# SakuraIo.net
KiCad netlist of a schematic drawn in EAGLE
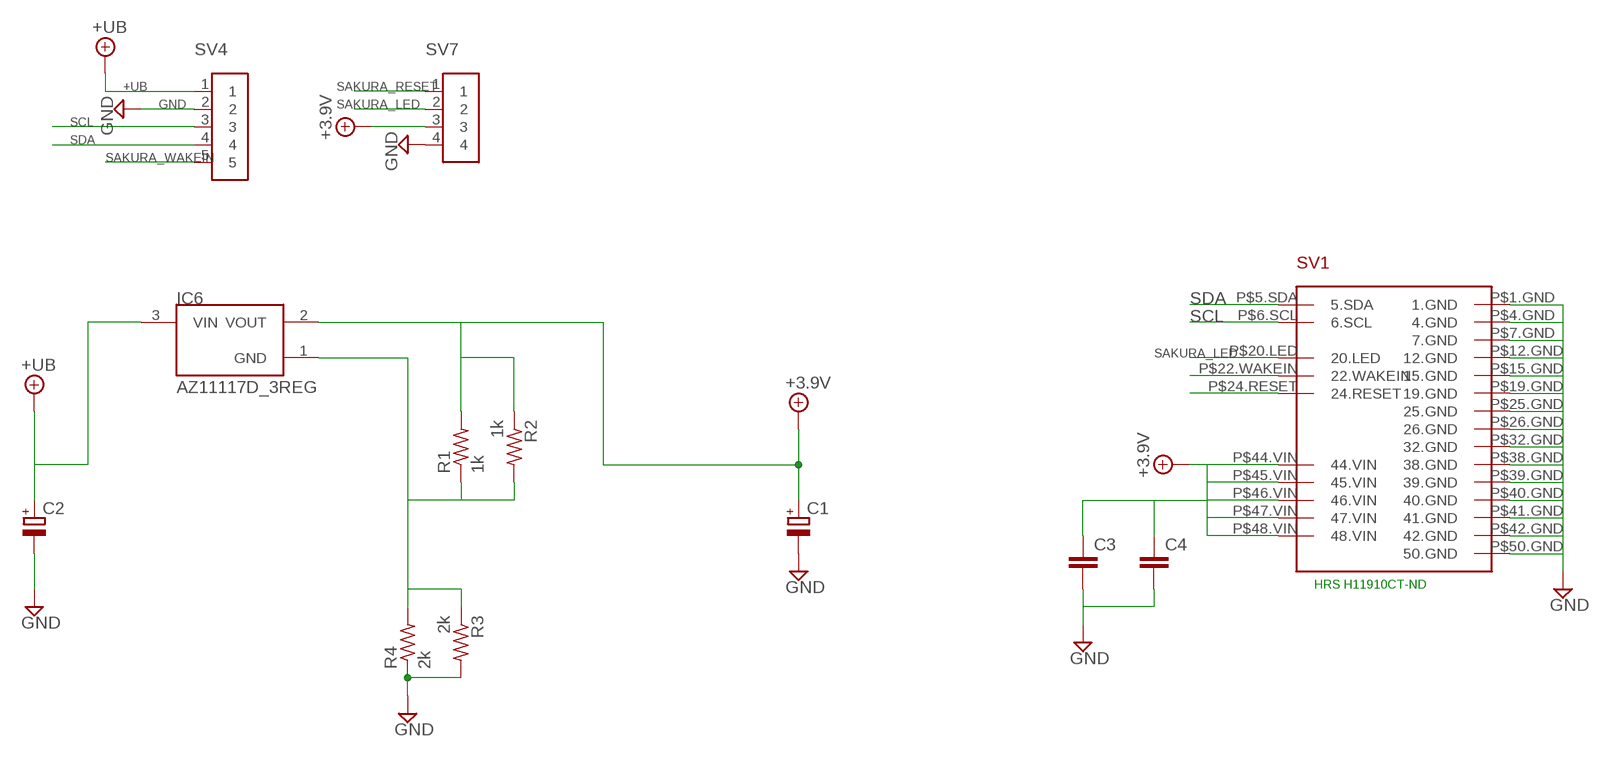
[diagram p0: schematic, sheet 1]

(export (version "E")
  (design (tool "Eeschema 10.0.6"))
  (components
    (comp (ref "C1")
      (value "CPOL-EUE2,5-6E")
      (footprint "eagle-import:E2,5-6E")
      (libsource (lib "eagle-import") (part "CPOL-EUE2,5-6E"))
    )
    (comp (ref "C2")
      (value "CPOL-EUE2,5-6E")
      (footprint "eagle-import:E2,5-6E")
      (libsource (lib "eagle-import") (part "CPOL-EUE2,5-6E"))
    )
    (comp (ref "C3")
      (value "C-EUC0603")
      (footprint "eagle-import:C0603")
      (libsource (lib "eagle-import") (part "C-EUC0603"))
    )
    (comp (ref "C4")
      (value "C-EUC0603")
      (footprint "eagle-import:C0603")
      (libsource (lib "eagle-import") (part "C-EUC0603"))
    )
    (comp (ref "IC6")
      (value "AZ11117D_3REG")
      (footprint "eagle-import:TO252")
      (libsource (lib "eagle-import") (part "AZ11117D_3REG"))
    )
    (comp (ref "R1")
      (value "1k")
      (footprint "eagle-import:0204_7")
      (libsource (lib "eagle-import") (part "R-US_0204/7"))
    )
    (comp (ref "R2")
      (value "1k")
      (footprint "eagle-import:R0603")
      (libsource (lib "eagle-import") (part "resistor_R-US_R0603"))
    )
    (comp (ref "R3")
      (value "2k")
      (footprint "eagle-import:R0603")
      (libsource (lib "eagle-import") (part "resistor_R-US_R0603"))
    )
    (comp (ref "R4")
      (value "2k")
      (footprint "eagle-import:0204_7")
      (libsource (lib "eagle-import") (part "R-US_0204/7"))
    )
    (comp (ref "SV1")
      (value "SAKURA-HRS-CONNECTOR50")
      (footprint "eagle-import:SAKURA-HRS-CONNECTOR50")
      (libsource (lib "eagle-import") (part "SAKURA-HRS-CONNECTOR50"))
    )
    (comp (ref "SV4")
      (value "PINHEADER_5_2.54MM")
      (footprint "eagle-import:PINHEADER_5_2.54MM")
      (libsource (lib "eagle-import") (part "PINHEADER_5_2.54MM"))
    )
    (comp (ref "SV7")
      (value "PINHEADER_4_2.54MM")
      (footprint "eagle-import:PINHEADER_4_2.54MM")
      (libsource (lib "eagle-import") (part "PINHEADER_4_2.54MM"))
    )
  )
  (nets
    (net (code "1") (name "+3.9V") (class "Default")
      (node (ref "C1") (pin "+") (pinfunction "+_+") (pintype "passive"))
      (node (ref "C3") (pin "1") (pinfunction "1_1") (pintype "passive"))
      (node (ref "C4") (pin "1") (pinfunction "1_1") (pintype "passive"))
      (node (ref "IC6") (pin "2") (pinfunction "VOUT_2") (pintype "bidirectional"))
      (node (ref "R1") (pin "2") (pinfunction "2_2") (pintype "passive"))
      (node (ref "R2") (pin "1") (pinfunction "1_1") (pintype "passive"))
      (node (ref "SV1") (pin "P$44.VIN") (pinfunction "44.VIN_P$44.VIN") (pintype "bidirectional"))
      (node (ref "SV1") (pin "P$45.VIN") (pinfunction "45.VIN_P$45.VIN") (pintype "bidirectional"))
      (node (ref "SV1") (pin "P$46.VIN") (pinfunction "46.VIN_P$46.VIN") (pintype "bidirectional"))
      (node (ref "SV1") (pin "P$47.VIN") (pinfunction "47.VIN_P$47.VIN") (pintype "bidirectional"))
      (node (ref "SV1") (pin "P$48.VIN") (pinfunction "48.VIN_P$48.VIN") (pintype "bidirectional"))
      (node (ref "SV7") (pin "3") (pinfunction "3_3") (pintype "bidirectional"))
    )
    (net (code "2") (name "+UB") (class "Default")
      (node (ref "C2") (pin "+") (pinfunction "+_+") (pintype "passive"))
      (node (ref "IC6") (pin "3") (pinfunction "VIN_3") (pintype "bidirectional"))
      (node (ref "SV4") (pin "1") (pinfunction "1_1") (pintype "bidirectional"))
    )
    (net (code "3") (name "/SAKURA_LED") (class "Default")
      (node (ref "SV1") (pin "P$20.LED") (pinfunction "20.LED_P$20.LED") (pintype "bidirectional"))
      (node (ref "SV7") (pin "2") (pinfunction "2_2") (pintype "bidirectional"))
    )
    (net (code "4") (name "/SAKURA_RESET") (class "Default")
      (node (ref "SV1") (pin "P$24.RESET") (pinfunction "24.RESET_P$24.RESET") (pintype "bidirectional"))
      (node (ref "SV7") (pin "1") (pinfunction "1_1") (pintype "bidirectional"))
    )
    (net (code "5") (name "/SAKURA_WAKEIN") (class "Default")
      (node (ref "SV1") (pin "P$22.WAKEIN") (pinfunction "22.WAKEIN_P$22.WAKEIN") (pintype "bidirectional"))
      (node (ref "SV4") (pin "5") (pinfunction "5_5") (pintype "bidirectional"))
    )
    (net (code "6") (name "/SCL") (class "Default")
      (node (ref "SV1") (pin "P$6.SCL") (pinfunction "6.SCL_P$6.SCL") (pintype "bidirectional"))
      (node (ref "SV4") (pin "3") (pinfunction "3_3") (pintype "bidirectional"))
    )
    (net (code "7") (name "/SDA") (class "Default")
      (node (ref "SV1") (pin "P$5.SDA") (pinfunction "5.SDA_P$5.SDA") (pintype "bidirectional"))
      (node (ref "SV4") (pin "4") (pinfunction "4_4") (pintype "bidirectional"))
    )
    (net (code "8") (name "GND") (class "Default")
      (node (ref "C1") (pin "-") (pinfunction "-_-") (pintype "passive"))
      (node (ref "C2") (pin "-") (pinfunction "-_-") (pintype "passive"))
      (node (ref "C3") (pin "2") (pinfunction "2_2") (pintype "passive"))
      (node (ref "C4") (pin "2") (pinfunction "2_2") (pintype "passive"))
      (node (ref "R3") (pin "2") (pinfunction "2_2") (pintype "passive"))
      (node (ref "R4") (pin "1") (pinfunction "1_1") (pintype "passive"))
      (node (ref "SV1") (pin "P$1.GND") (pinfunction "1.GND_P$1.GND") (pintype "bidirectional"))
      (node (ref "SV1") (pin "P$12.GND") (pinfunction "12.GND_P$12.GND") (pintype "bidirectional"))
      (node (ref "SV1") (pin "P$15.GND") (pinfunction "15.GND_P$15.GND") (pintype "bidirectional"))
      (node (ref "SV1") (pin "P$19.GND") (pinfunction "19.GND_P$19.GND") (pintype "bidirectional"))
      (node (ref "SV1") (pin "P$25.GND") (pinfunction "25.GND_P$25.GND") (pintype "bidirectional"))
      (node (ref "SV1") (pin "P$26.GND") (pinfunction "26.GND_P$26.GND") (pintype "bidirectional"))
      (node (ref "SV1") (pin "P$32.GND") (pinfunction "32.GND_P$32.GND") (pintype "bidirectional"))
      (node (ref "SV1") (pin "P$38.GND") (pinfunction "38.GND_P$38.GND") (pintype "bidirectional"))
      (node (ref "SV1") (pin "P$39.GND") (pinfunction "39.GND_P$39.GND") (pintype "bidirectional"))
      (node (ref "SV1") (pin "P$4.GND") (pinfunction "4.GND_P$4.GND") (pintype "bidirectional"))
      (node (ref "SV1") (pin "P$40.GND") (pinfunction "40.GND_P$40.GND") (pintype "bidirectional"))
      (node (ref "SV1") (pin "P$41.GND") (pinfunction "41.GND_P$41.GND") (pintype "bidirectional"))
      (node (ref "SV1") (pin "P$42.GND") (pinfunction "42.GND_P$42.GND") (pintype "bidirectional"))
      (node (ref "SV1") (pin "P$50.GND") (pinfunction "50.GND_P$50.GND") (pintype "bidirectional"))
      (node (ref "SV1") (pin "P$7.GND") (pinfunction "7.GND_P$7.GND") (pintype "bidirectional"))
      (node (ref "SV4") (pin "2") (pinfunction "2_2") (pintype "bidirectional"))
      (node (ref "SV7") (pin "4") (pinfunction "4_4") (pintype "bidirectional"))
    )
    (net (code "9") (name "Net-(IC6-GND)") (class "Default")
      (node (ref "IC6") (pin "1") (pinfunction "GND_1") (pintype "bidirectional"))
      (node (ref "R1") (pin "1") (pinfunction "1_1") (pintype "passive"))
      (node (ref "R2") (pin "2") (pinfunction "2_2") (pintype "passive"))
      (node (ref "R3") (pin "1") (pinfunction "1_1") (pintype "passive"))
      (node (ref "R4") (pin "2") (pinfunction "2_2") (pintype "passive"))
    )
  )
)
